# esquematico_inicial_para_a_FRMF_test.net
KiCad netlist of a schematic drawn in EAGLE
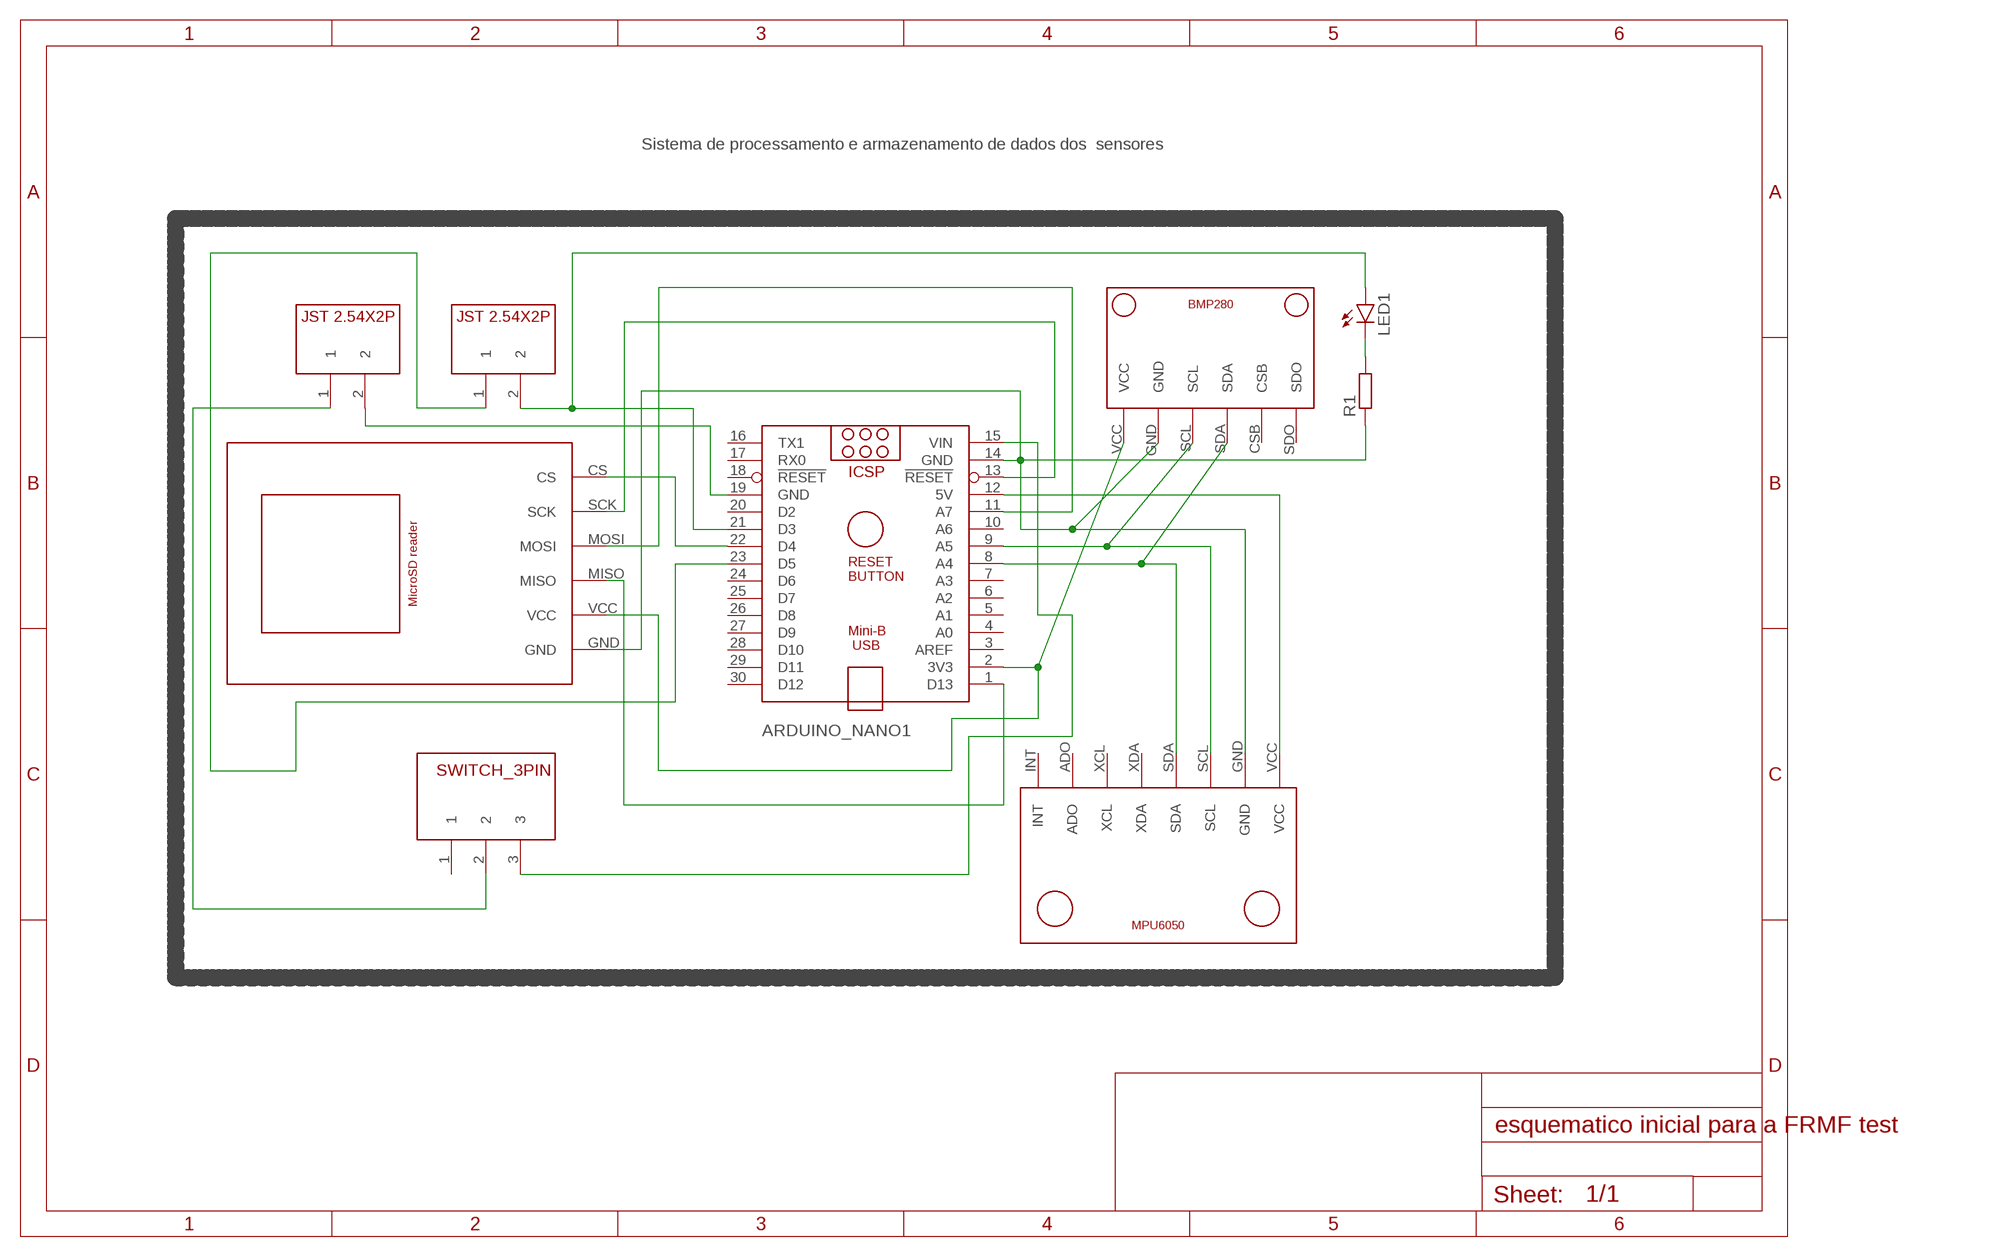
[diagram p0: schematic, sheet 1]

(export (version "E")
  (design (tool "Eeschema 10.0.6"))
  (components
    (comp (ref "ARDUINO_NANO1")
      (value "ARDUINO_NANO")
      (footprint "eagle-import:ARDUINO_NANO")
      (libsource (lib "eagle-import") (part "ARDUINO_NANO"))
    )
    (comp (ref "LED1")
      (value "LED5MM")
      (footprint "eagle-import:LED5MM")
      (libsource (lib "eagle-import") (part "LED5MM"))
    )
    (comp (ref "R1")
      (value "R-EU_0207/10")
      (footprint "eagle-import:0207_10")
      (libsource (lib "eagle-import") (part "R-EU_0207/10"))
    )
    (comp (ref "U$1")
      (value "BMP280V1")
      (footprint "eagle-import:BMP280_FOOTPRINT")
      (libsource (lib "eagle-import") (part "BMP280V1"))
    )
    (comp (ref "U$2")
      (value "MPU6050V1")
      (footprint "eagle-import:MPU6050_FOOTPRINT")
      (libsource (lib "eagle-import") (part "MPU6050V1"))
    )
    (comp (ref "U$3")
      (value "MICROSD_READER")
      (footprint "eagle-import:MICROSD_READER_FOOTPRINT")
      (libsource (lib "eagle-import") (part "MICROSD_READER"))
    )
    (comp (ref "U$4")
      (value "SWITCH_3PIN")
      (footprint "eagle-import:SWITCH_3PIN")
      (libsource (lib "eagle-import") (part "SWITCH_3PIN"))
    )
    (comp (ref "U$5")
      (value "JST2.54X2P")
      (footprint "eagle-import:JST2.54X2P_FOOTPRINT")
      (libsource (lib "eagle-import") (part "JST2.54X2P"))
    )
    (comp (ref "U$6")
      (value "JST2.54X2P")
      (footprint "eagle-import:JST2.54X2P_FOOTPRINT")
      (libsource (lib "eagle-import") (part "JST2.54X2P"))
    )
  )
  (nets
    (net (code "1") (name "Net-(ARDUINO_NANO1-3V3)") (class "Default")
      (node (ref "ARDUINO_NANO1") (pin "2") (pinfunction "3V3_2") (pintype "output"))
      (node (ref "U$1") (pin "VCC") (pinfunction "VCC_VCC") (pintype "bidirectional"))
      (node (ref "U$3") (pin "VCC") (pinfunction "VCC_VCC") (pintype "bidirectional"))
    )
    (net (code "2") (name "Net-(ARDUINO_NANO1-5V)") (class "Default")
      (node (ref "ARDUINO_NANO1") (pin "12") (pinfunction "5V_12") (pintype "power_in"))
      (node (ref "U$2") (pin "VCC") (pinfunction "VCC_VCC") (pintype "bidirectional"))
    )
    (net (code "3") (name "Net-(ARDUINO_NANO1-A4)") (class "Default")
      (node (ref "ARDUINO_NANO1") (pin "8") (pinfunction "A4_8") (pintype "bidirectional"))
      (node (ref "U$1") (pin "SDA") (pinfunction "SDA_SDA") (pintype "bidirectional"))
      (node (ref "U$2") (pin "SDA") (pinfunction "SDA_SDA") (pintype "bidirectional"))
    )
    (net (code "4") (name "Net-(ARDUINO_NANO1-A5)") (class "Default")
      (node (ref "ARDUINO_NANO1") (pin "9") (pinfunction "A5_9") (pintype "bidirectional"))
      (node (ref "U$1") (pin "SCL") (pinfunction "SCL_SCL") (pintype "bidirectional"))
      (node (ref "U$2") (pin "SCL") (pinfunction "SCL_SCL") (pintype "bidirectional"))
    )
    (net (code "5") (name "Net-(ARDUINO_NANO1-A7)") (class "Default")
      (node (ref "ARDUINO_NANO1") (pin "11") (pinfunction "A7_11") (pintype "bidirectional"))
      (node (ref "U$3") (pin "MOSI") (pinfunction "MOSI_MOSI") (pintype "bidirectional"))
    )
    (net (code "6") (name "Net-(ARDUINO_NANO1-D3)") (class "Default")
      (node (ref "ARDUINO_NANO1") (pin "21") (pinfunction "D3_21") (pintype "bidirectional"))
      (node (ref "LED1") (pin "A") (pinfunction "A_A") (pintype "passive"))
      (node (ref "U$5") (pin "2") (pinfunction "2_2") (pintype "bidirectional"))
    )
    (net (code "7") (name "Net-(ARDUINO_NANO1-D4)") (class "Default")
      (node (ref "ARDUINO_NANO1") (pin "22") (pinfunction "D4_22") (pintype "bidirectional"))
      (node (ref "U$3") (pin "CS") (pinfunction "CS_CS") (pintype "bidirectional"))
    )
    (net (code "8") (name "Net-(ARDUINO_NANO1-D5)") (class "Default")
      (node (ref "ARDUINO_NANO1") (pin "23") (pinfunction "D5_23") (pintype "bidirectional"))
      (node (ref "U$5") (pin "1") (pinfunction "1_1") (pintype "bidirectional"))
    )
    (net (code "9") (name "Net-(ARDUINO_NANO1-D13)") (class "Default")
      (node (ref "ARDUINO_NANO1") (pin "1") (pinfunction "D13_1") (pintype "bidirectional"))
      (node (ref "U$3") (pin "MISO") (pinfunction "MISO_MISO") (pintype "bidirectional"))
    )
    (net (code "10") (name "Net-(ARDUINO_NANO1-GND-Pad14)") (class "Default")
      (node (ref "ARDUINO_NANO1") (pin "14") (pinfunction "GND_14") (pintype "power_in"))
      (node (ref "R1") (pin "1") (pinfunction "1_1") (pintype "passive"))
      (node (ref "U$1") (pin "GND") (pinfunction "GND_GND") (pintype "bidirectional"))
      (node (ref "U$2") (pin "GND") (pinfunction "GND_GND") (pintype "bidirectional"))
      (node (ref "U$3") (pin "GND") (pinfunction "GND_GND") (pintype "bidirectional"))
    )
    (net (code "11") (name "Net-(ARDUINO_NANO1-GND-Pad19)") (class "Default")
      (node (ref "ARDUINO_NANO1") (pin "19") (pinfunction "GND_19") (pintype "power_in"))
      (node (ref "U$6") (pin "2") (pinfunction "2_2") (pintype "bidirectional"))
    )
    (net (code "12") (name "Net-(ARDUINO_NANO1-VIN)") (class "Default")
      (node (ref "ARDUINO_NANO1") (pin "15") (pinfunction "VIN_15") (pintype "power_in"))
      (node (ref "U$4") (pin "3") (pinfunction "3_3") (pintype "bidirectional"))
    )
    (net (code "13") (name "Net-(ARDUINO_NANO1-~{RESET}-Pad13)") (class "Default")
      (node (ref "ARDUINO_NANO1") (pin "13") (pinfunction "~{RESET}_13") (pintype "input"))
      (node (ref "U$3") (pin "SCK") (pinfunction "SCK_SCK") (pintype "bidirectional"))
    )
    (net (code "14") (name "Net-(LED1-C)") (class "Default")
      (node (ref "LED1") (pin "K") (pinfunction "C_K") (pintype "passive"))
      (node (ref "R1") (pin "2") (pinfunction "2_2") (pintype "passive"))
    )
    (net (code "15") (name "Net-(U$4-Pad2)") (class "Default")
      (node (ref "U$4") (pin "2") (pinfunction "2_2") (pintype "bidirectional"))
      (node (ref "U$6") (pin "1") (pinfunction "1_1") (pintype "bidirectional"))
    )
    (net (code "16") (name "unconnected-(ARDUINO_NANO1-A0-Pad4)") (class "Default")
      (node (ref "ARDUINO_NANO1") (pin "4") (pinfunction "A0_4") (pintype "bidirectional"))
    )
    (net (code "17") (name "unconnected-(ARDUINO_NANO1-A1-Pad5)") (class "Default")
      (node (ref "ARDUINO_NANO1") (pin "5") (pinfunction "A1_5") (pintype "bidirectional"))
    )
    (net (code "18") (name "unconnected-(ARDUINO_NANO1-A2-Pad6)") (class "Default")
      (node (ref "ARDUINO_NANO1") (pin "6") (pinfunction "A2_6") (pintype "bidirectional"))
    )
    (net (code "19") (name "unconnected-(ARDUINO_NANO1-A3-Pad7)") (class "Default")
      (node (ref "ARDUINO_NANO1") (pin "7") (pinfunction "A3_7") (pintype "bidirectional"))
    )
    (net (code "20") (name "unconnected-(ARDUINO_NANO1-A6-Pad10)") (class "Default")
      (node (ref "ARDUINO_NANO1") (pin "10") (pinfunction "A6_10") (pintype "bidirectional"))
    )
    (net (code "21") (name "unconnected-(ARDUINO_NANO1-AREF-Pad3)") (class "Default")
      (node (ref "ARDUINO_NANO1") (pin "3") (pinfunction "AREF_3") (pintype "input"))
    )
    (net (code "22") (name "unconnected-(ARDUINO_NANO1-D2-Pad20)") (class "Default")
      (node (ref "ARDUINO_NANO1") (pin "20") (pinfunction "D2_20") (pintype "bidirectional"))
    )
    (net (code "23") (name "unconnected-(ARDUINO_NANO1-D6-Pad24)") (class "Default")
      (node (ref "ARDUINO_NANO1") (pin "24") (pinfunction "D6_24") (pintype "bidirectional"))
    )
    (net (code "24") (name "unconnected-(ARDUINO_NANO1-D7-Pad25)") (class "Default")
      (node (ref "ARDUINO_NANO1") (pin "25") (pinfunction "D7_25") (pintype "bidirectional"))
    )
    (net (code "25") (name "unconnected-(ARDUINO_NANO1-D8-Pad26)") (class "Default")
      (node (ref "ARDUINO_NANO1") (pin "26") (pinfunction "D8_26") (pintype "bidirectional"))
    )
    (net (code "26") (name "unconnected-(ARDUINO_NANO1-D9-Pad27)") (class "Default")
      (node (ref "ARDUINO_NANO1") (pin "27") (pinfunction "D9_27") (pintype "bidirectional"))
    )
    (net (code "27") (name "unconnected-(ARDUINO_NANO1-D10-Pad28)") (class "Default")
      (node (ref "ARDUINO_NANO1") (pin "28") (pinfunction "D10_28") (pintype "bidirectional"))
    )
    (net (code "28") (name "unconnected-(ARDUINO_NANO1-D11-Pad29)") (class "Default")
      (node (ref "ARDUINO_NANO1") (pin "29") (pinfunction "D11_29") (pintype "bidirectional"))
    )
    (net (code "29") (name "unconnected-(ARDUINO_NANO1-D12-Pad30)") (class "Default")
      (node (ref "ARDUINO_NANO1") (pin "30") (pinfunction "D12_30") (pintype "bidirectional"))
    )
    (net (code "30") (name "unconnected-(ARDUINO_NANO1-RX0-Pad17)") (class "Default")
      (node (ref "ARDUINO_NANO1") (pin "17") (pinfunction "RX0_17") (pintype "bidirectional"))
    )
    (net (code "31") (name "unconnected-(ARDUINO_NANO1-TX1-Pad16)") (class "Default")
      (node (ref "ARDUINO_NANO1") (pin "16") (pinfunction "TX1_16") (pintype "bidirectional"))
    )
    (net (code "32") (name "unconnected-(ARDUINO_NANO1-~{RESET}-Pad18)") (class "Default")
      (node (ref "ARDUINO_NANO1") (pin "18") (pinfunction "~{RESET}_18") (pintype "input"))
    )
    (net (code "33") (name "unconnected-(U$1-PadCSB)") (class "Default")
      (node (ref "U$1") (pin "CSB") (pinfunction "CSB_CSB") (pintype "bidirectional"))
    )
    (net (code "34") (name "unconnected-(U$1-PadSDO)") (class "Default")
      (node (ref "U$1") (pin "SDO") (pinfunction "SDO_SDO") (pintype "bidirectional"))
    )
    (net (code "35") (name "unconnected-(U$2-PadADO)") (class "Default")
      (node (ref "U$2") (pin "ADO") (pinfunction "ADO_ADO") (pintype "bidirectional"))
    )
    (net (code "36") (name "unconnected-(U$2-PadINT)") (class "Default")
      (node (ref "U$2") (pin "INT") (pinfunction "INT_INT") (pintype "bidirectional"))
    )
    (net (code "37") (name "unconnected-(U$2-PadXCL)") (class "Default")
      (node (ref "U$2") (pin "XCL") (pinfunction "XCL_XCL") (pintype "bidirectional"))
    )
    (net (code "38") (name "unconnected-(U$2-PadXDA)") (class "Default")
      (node (ref "U$2") (pin "XDA") (pinfunction "XDA_XDA") (pintype "bidirectional"))
    )
    (net (code "39") (name "unconnected-(U$4-Pad1)") (class "Default")
      (node (ref "U$4") (pin "1") (pinfunction "1_1") (pintype "bidirectional"))
    )
  )
)
